# wearable_base.net
KiCad netlist of a schematic drawn in EAGLE
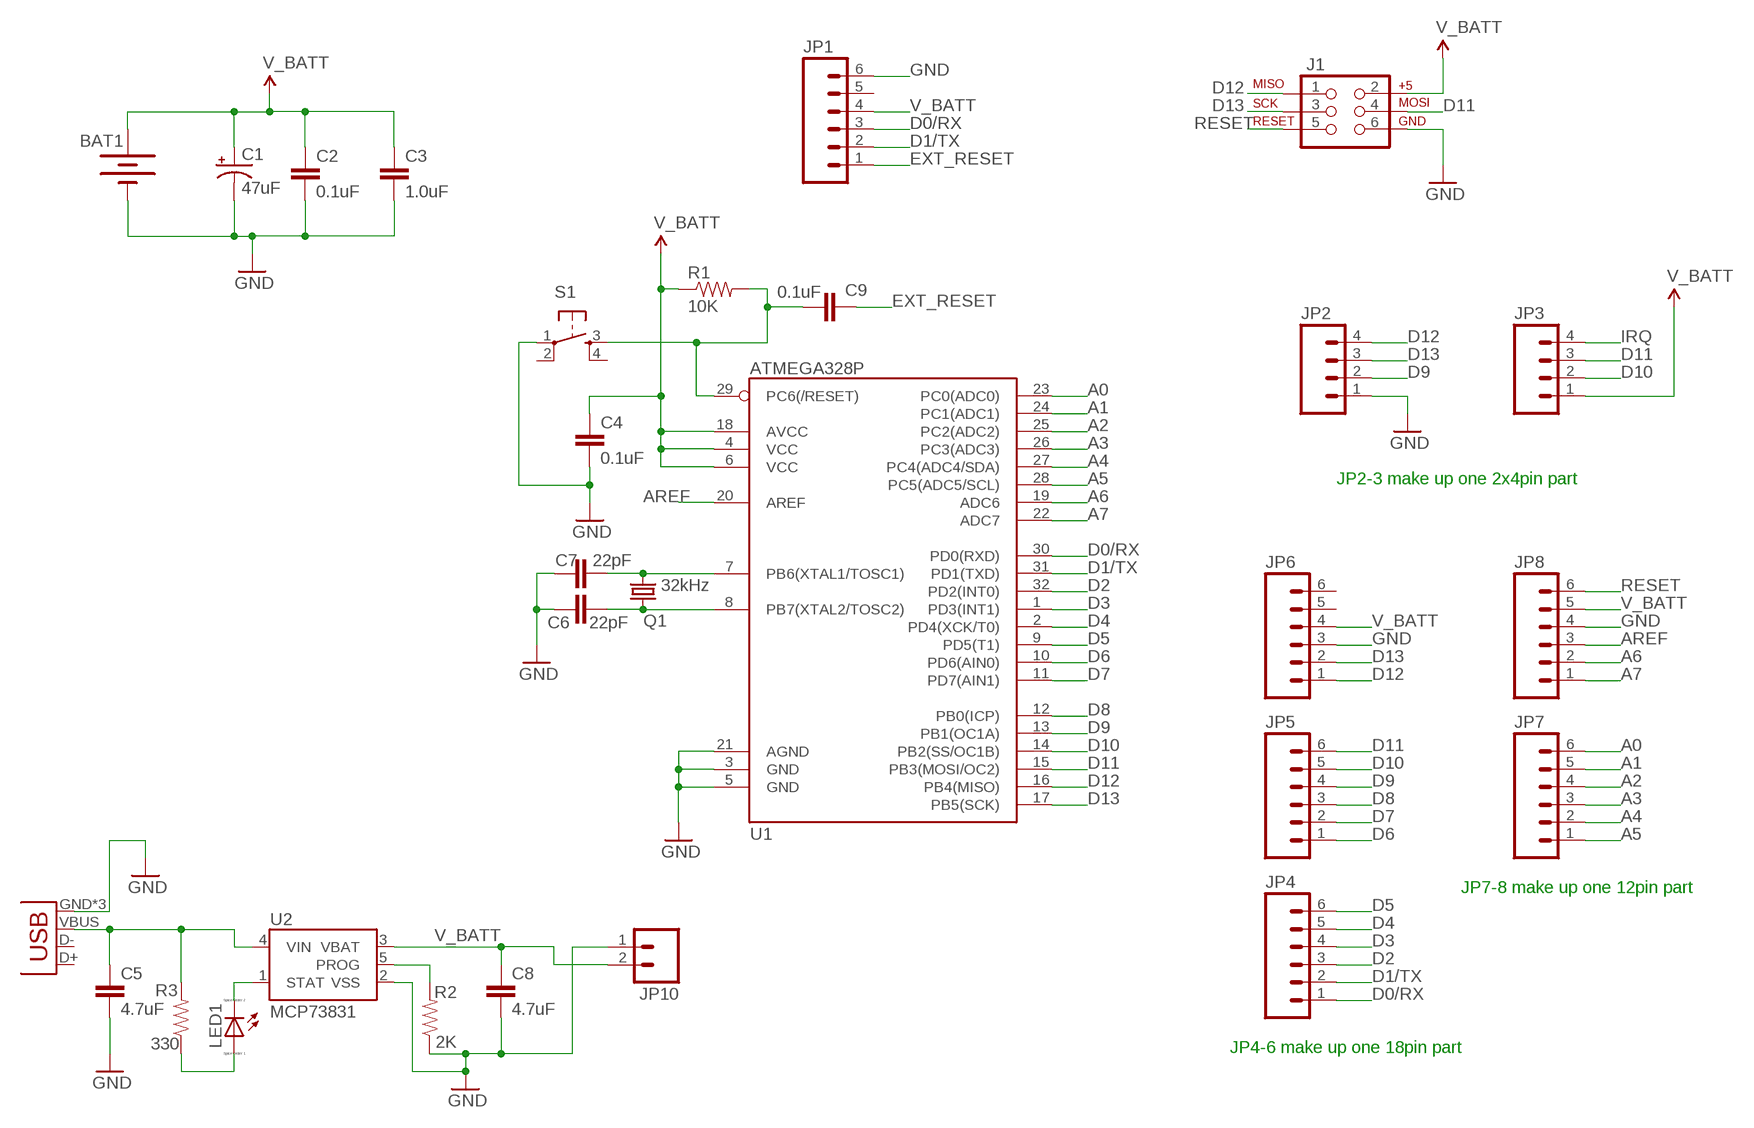
[diagram p0: schematic, sheet 1]

(export (version "E")
  (design (tool "Eeschema 10.0.6"))
  (components
    (comp (ref "BAT1")
      (value "20mm coincell")
      (footprint "eagle-import:BATTCON_20MM_4LEGS")
      (libsource (lib "eagle-import") (part "BATTERY20MM_4LEGS"))
    )
    (comp (ref "C1")
      (value "47uF")
      (footprint "eagle-import:EIA3216")
      (libsource (lib "eagle-import") (part "CAP_POL1206"))
    )
    (comp (ref "C2")
      (value "0.1uF")
      (footprint "eagle-import:0603-CAP")
      (libsource (lib "eagle-import") (part "0.1UF-25V-5%(0603)"))
    )
    (comp (ref "C3")
      (value "1.0uF")
      (footprint "eagle-import:0603-CAP")
      (libsource (lib "eagle-import") (part "1.0UF-16V-10%(0603)"))
    )
    (comp (ref "C4")
      (value "0.1uF")
      (footprint "eagle-import:0603-CAP")
      (libsource (lib "eagle-import") (part "0.1UF-25V-5%(0603)"))
    )
    (comp (ref "C5")
      (value "4.7uF")
      (footprint "eagle-import:0603-CAP")
      (libsource (lib "eagle-import") (part "CAP0603-CAP"))
    )
    (comp (ref "C6")
      (value "22pF")
      (footprint "eagle-import:0603-CAP")
      (libsource (lib "eagle-import") (part "22PF-50V-5%(0603)"))
    )
    (comp (ref "C7")
      (value "22pF")
      (footprint "eagle-import:0603-CAP")
      (libsource (lib "eagle-import") (part "22PF-50V-5%(0603)"))
    )
    (comp (ref "C8")
      (value "4.7uF")
      (footprint "eagle-import:0603-CAP")
      (libsource (lib "eagle-import") (part "CAP0603-CAP"))
    )
    (comp (ref "C9")
      (value "0.1uF")
      (footprint "eagle-import:0603-CAP")
      (libsource (lib "eagle-import") (part "0.1UF-25V-5%(0603)"))
    )
    (comp (ref "J1")
      (value "AVR_SPI_PRG_6PTH")
      (footprint "eagle-import:2X3")
      (libsource (lib "eagle-import") (part "AVR_SPI_PRG_6PTH"))
    )
    (comp (ref "JP1")
      (value "M06SIP")
      (footprint "eagle-import:1X06")
      (libsource (lib "eagle-import") (part "M06SIP"))
    )
    (comp (ref "JP2")
      (value "M04PTH")
      (footprint "eagle-import:1X04")
      (libsource (lib "eagle-import") (part "M04PTH"))
    )
    (comp (ref "JP3")
      (value "M04PTH")
      (footprint "eagle-import:1X04")
      (libsource (lib "eagle-import") (part "M04PTH"))
    )
    (comp (ref "JP4")
      (value "M06SIP")
      (footprint "eagle-import:1X06")
      (libsource (lib "eagle-import") (part "M06SIP"))
    )
    (comp (ref "JP5")
      (value "M06SIP")
      (footprint "eagle-import:1X06")
      (libsource (lib "eagle-import") (part "M06SIP"))
    )
    (comp (ref "JP6")
      (value "M06SIP")
      (footprint "eagle-import:1X06")
      (libsource (lib "eagle-import") (part "M06SIP"))
    )
    (comp (ref "JP7")
      (value "M06SIP")
      (footprint "eagle-import:1X06")
      (libsource (lib "eagle-import") (part "M06SIP"))
    )
    (comp (ref "JP8")
      (value "M06SIP")
      (footprint "eagle-import:1X06")
      (libsource (lib "eagle-import") (part "M06SIP"))
    )
    (comp (ref "JP9")
      (value "USB-MICROB")
      (footprint "eagle-import:USB-MICROB")
      (libsource (lib "eagle-import") (part "USB-MICROB"))
    )
    (comp (ref "JP10")
      (value "M02JST-PTH-2")
      (footprint "eagle-import:JST-2-PTH")
      (libsource (lib "eagle-import") (part "M02JST-PTH-2"))
    )
    (comp (ref "LED1")
      (value "LED_ESML0603")
      (footprint "eagle-import:LED_SML0603")
      (libsource (lib "eagle-import") (part "LED_ESML0603"))
    )
    (comp (ref "Q1")
      (value "32kHz")
      (footprint "eagle-import:TC26H")
      (libsource (lib "eagle-import") (part "CRYSTALTC26H"))
    )
    (comp (ref "R1")
      (value "10K")
      (footprint "eagle-import:0603-RES")
      (libsource (lib "eagle-import") (part "RESISTOR0603-RES"))
    )
    (comp (ref "R2")
      (value "2K")
      (footprint "eagle-import:0603-RES")
      (libsource (lib "eagle-import") (part "RESISTOR0603-RES"))
    )
    (comp (ref "R3")
      (value "330")
      (footprint "eagle-import:0603-RES")
      (libsource (lib "eagle-import") (part "RESISTOR0603-RES"))
    )
    (comp (ref "S1")
      (value "TAC_SWITCHSMD")
      (footprint "eagle-import:TACTILE_SWITCH_SMD")
      (libsource (lib "eagle-import") (part "TAC_SWITCHSMD"))
    )
    (comp (ref "U1")
      (value "ATMEGA328P")
      (footprint "eagle-import:TQFP32-08")
      (libsource (lib "eagle-import") (part "ATMEGA328_SMT"))
    )
    (comp (ref "U2")
      (value "MCP73831")
      (footprint "eagle-import:SOT23-5")
      (libsource (lib "eagle-import") (part "MCP73831"))
    )
  )
  (nets
    (net (code "1") (name "/A0") (class "Default")
      (node (ref "JP7") (pin "6") (pinfunction "6_6") (pintype "passive"))
      (node (ref "U1") (pin "23") (pinfunction "PC0(ADC0)_23") (pintype "bidirectional"))
    )
    (net (code "2") (name "/A1") (class "Default")
      (node (ref "JP7") (pin "5") (pinfunction "5_5") (pintype "passive"))
      (node (ref "U1") (pin "24") (pinfunction "PC1(ADC1)_24") (pintype "bidirectional"))
    )
    (net (code "3") (name "/A2") (class "Default")
      (node (ref "JP7") (pin "4") (pinfunction "4_4") (pintype "passive"))
      (node (ref "U1") (pin "25") (pinfunction "PC2(ADC2)_25") (pintype "bidirectional"))
    )
    (net (code "4") (name "/A3") (class "Default")
      (node (ref "JP7") (pin "3") (pinfunction "3_3") (pintype "passive"))
      (node (ref "U1") (pin "26") (pinfunction "PC3(ADC3)_26") (pintype "bidirectional"))
    )
    (net (code "5") (name "/A4") (class "Default")
      (node (ref "JP7") (pin "2") (pinfunction "2_2") (pintype "passive"))
      (node (ref "U1") (pin "27") (pinfunction "PC4(ADC4/SDA)_27") (pintype "bidirectional"))
    )
    (net (code "6") (name "/A5") (class "Default")
      (node (ref "JP7") (pin "1") (pinfunction "1_1") (pintype "passive"))
      (node (ref "U1") (pin "28") (pinfunction "PC5(ADC5/SCL)_28") (pintype "bidirectional"))
    )
    (net (code "7") (name "/A6") (class "Default")
      (node (ref "JP8") (pin "2") (pinfunction "2_2") (pintype "passive"))
      (node (ref "U1") (pin "19") (pinfunction "ADC6_19") (pintype "bidirectional"))
    )
    (net (code "8") (name "/A7") (class "Default")
      (node (ref "JP8") (pin "1") (pinfunction "1_1") (pintype "passive"))
      (node (ref "U1") (pin "22") (pinfunction "ADC7_22") (pintype "bidirectional"))
    )
    (net (code "9") (name "/AREF") (class "Default")
      (node (ref "JP8") (pin "3") (pinfunction "3_3") (pintype "passive"))
      (node (ref "U1") (pin "20") (pinfunction "AREF_20") (pintype "bidirectional"))
    )
    (net (code "10") (name "/D0{slash}RX") (class "Default")
      (node (ref "JP1") (pin "3") (pinfunction "3_3") (pintype "passive"))
      (node (ref "JP4") (pin "1") (pinfunction "1_1") (pintype "passive"))
      (node (ref "U1") (pin "30") (pinfunction "PD0(RXD)_30") (pintype "bidirectional"))
    )
    (net (code "11") (name "/D1{slash}TX") (class "Default")
      (node (ref "JP1") (pin "2") (pinfunction "2_2") (pintype "passive"))
      (node (ref "JP4") (pin "2") (pinfunction "2_2") (pintype "passive"))
      (node (ref "U1") (pin "31") (pinfunction "PD1(TXD)_31") (pintype "bidirectional"))
    )
    (net (code "12") (name "/D2") (class "Default")
      (node (ref "JP4") (pin "3") (pinfunction "3_3") (pintype "passive"))
      (node (ref "U1") (pin "32") (pinfunction "PD2(INT0)_32") (pintype "bidirectional"))
    )
    (net (code "13") (name "/D3") (class "Default")
      (node (ref "JP4") (pin "4") (pinfunction "4_4") (pintype "passive"))
      (node (ref "U1") (pin "1") (pinfunction "PD3(INT1)_1") (pintype "bidirectional"))
    )
    (net (code "14") (name "/D4") (class "Default")
      (node (ref "JP4") (pin "5") (pinfunction "5_5") (pintype "passive"))
      (node (ref "U1") (pin "2") (pinfunction "PD4(XCK/T0)_2") (pintype "bidirectional"))
    )
    (net (code "15") (name "/D5") (class "Default")
      (node (ref "JP4") (pin "6") (pinfunction "6_6") (pintype "passive"))
      (node (ref "U1") (pin "9") (pinfunction "PD5(T1)_9") (pintype "bidirectional"))
    )
    (net (code "16") (name "/D6") (class "Default")
      (node (ref "JP5") (pin "1") (pinfunction "1_1") (pintype "passive"))
      (node (ref "U1") (pin "10") (pinfunction "PD6(AIN0)_10") (pintype "bidirectional"))
    )
    (net (code "17") (name "/D7") (class "Default")
      (node (ref "JP5") (pin "2") (pinfunction "2_2") (pintype "passive"))
      (node (ref "U1") (pin "11") (pinfunction "PD7(AIN1)_11") (pintype "bidirectional"))
    )
    (net (code "18") (name "/D8") (class "Default")
      (node (ref "JP5") (pin "3") (pinfunction "3_3") (pintype "passive"))
      (node (ref "U1") (pin "12") (pinfunction "PB0(ICP)_12") (pintype "bidirectional"))
    )
    (net (code "19") (name "/D9") (class "Default")
      (node (ref "JP2") (pin "2") (pinfunction "2_2") (pintype "passive"))
      (node (ref "JP5") (pin "4") (pinfunction "4_4") (pintype "passive"))
      (node (ref "U1") (pin "13") (pinfunction "PB1(OC1A)_13") (pintype "bidirectional"))
    )
    (net (code "20") (name "/D10") (class "Default")
      (node (ref "JP3") (pin "2") (pinfunction "2_2") (pintype "passive"))
      (node (ref "JP5") (pin "5") (pinfunction "5_5") (pintype "passive"))
      (node (ref "U1") (pin "14") (pinfunction "PB2(SS/OC1B)_14") (pintype "bidirectional"))
    )
    (net (code "21") (name "/D11") (class "Default")
      (node (ref "J1") (pin "4") (pinfunction "4_4") (pintype "passive"))
      (node (ref "JP3") (pin "3") (pinfunction "3_3") (pintype "passive"))
      (node (ref "JP5") (pin "6") (pinfunction "6_6") (pintype "passive"))
      (node (ref "U1") (pin "15") (pinfunction "PB3(MOSI/OC2)_15") (pintype "bidirectional"))
    )
    (net (code "22") (name "/D12") (class "Default")
      (node (ref "J1") (pin "1") (pinfunction "1_1") (pintype "passive"))
      (node (ref "JP2") (pin "4") (pinfunction "4_4") (pintype "passive"))
      (node (ref "JP6") (pin "1") (pinfunction "1_1") (pintype "passive"))
      (node (ref "U1") (pin "16") (pinfunction "PB4(MISO)_16") (pintype "bidirectional"))
    )
    (net (code "23") (name "/D13") (class "Default")
      (node (ref "J1") (pin "3") (pinfunction "3_3") (pintype "passive"))
      (node (ref "JP2") (pin "3") (pinfunction "3_3") (pintype "passive"))
      (node (ref "JP6") (pin "2") (pinfunction "2_2") (pintype "passive"))
      (node (ref "U1") (pin "17") (pinfunction "PB5(SCK)_17") (pintype "bidirectional"))
    )
    (net (code "24") (name "/EXT_RESET") (class "Default")
      (node (ref "C9") (pin "1") (pinfunction "1_1") (pintype "passive"))
      (node (ref "JP1") (pin "1") (pinfunction "1_1") (pintype "passive"))
    )
    (net (code "25") (name "/IRQ") (class "Default")
      (node (ref "JP3") (pin "4") (pinfunction "4_4") (pintype "passive"))
    )
    (net (code "26") (name "/RESET") (class "Default")
      (node (ref "C9") (pin "2") (pinfunction "2_2") (pintype "passive"))
      (node (ref "J1") (pin "5") (pinfunction "5_5") (pintype "passive"))
      (node (ref "JP8") (pin "6") (pinfunction "6_6") (pintype "passive"))
      (node (ref "R1") (pin "2") (pinfunction "2_2") (pintype "passive"))
      (node (ref "S1") (pin "3") (pinfunction "3_3") (pintype "passive"))
      (node (ref "U1") (pin "29") (pinfunction "PC6(/RESET)_29") (pintype "bidirectional"))
    )
    (net (code "27") (name "GND") (class "Default")
      (node (ref "BAT1") (pin "2") (pinfunction "-_2") (pintype "power_in"))
      (node (ref "C1") (pin "C") (pinfunction "-_C") (pintype "passive"))
      (node (ref "C2") (pin "2") (pinfunction "2_2") (pintype "passive"))
      (node (ref "C3") (pin "2") (pinfunction "2_2") (pintype "passive"))
      (node (ref "C4") (pin "2") (pinfunction "2_2") (pintype "passive"))
      (node (ref "C5") (pin "2") (pinfunction "2_2") (pintype "passive"))
      (node (ref "C6") (pin "1") (pinfunction "1_1") (pintype "passive"))
      (node (ref "C7") (pin "2") (pinfunction "2_2") (pintype "passive"))
      (node (ref "C8") (pin "2") (pinfunction "2_2") (pintype "passive"))
      (node (ref "J1") (pin "6") (pinfunction "6_6") (pintype "passive"))
      (node (ref "JP1") (pin "6") (pinfunction "6_6") (pintype "passive"))
      (node (ref "JP10") (pin "1") (pinfunction "1_1") (pintype "passive"))
      (node (ref "JP2") (pin "1") (pinfunction "1_1") (pintype "passive"))
      (node (ref "JP6") (pin "3") (pinfunction "3_3") (pintype "passive"))
      (node (ref "JP8") (pin "4") (pinfunction "4_4") (pintype "passive"))
      (node (ref "JP9") (pin "GND") (pinfunction "GND_GND") (pintype "bidirectional"))
      (node (ref "JP9") (pin "MT1") (pinfunction "GND_MT1") (pintype "bidirectional"))
      (node (ref "JP9") (pin "MT2") (pinfunction "GND_MT2") (pintype "bidirectional"))
      (node (ref "R2") (pin "1") (pinfunction "1_1") (pintype "passive"))
      (node (ref "S1") (pin "1") (pinfunction "1_1") (pintype "passive"))
      (node (ref "U1") (pin "21") (pinfunction "AGND_21") (pintype "bidirectional"))
      (node (ref "U1") (pin "3") (pinfunction "GND_3") (pintype "bidirectional"))
      (node (ref "U1") (pin "5") (pinfunction "GND_5") (pintype "bidirectional"))
      (node (ref "U2") (pin "2") (pinfunction "VSS_2") (pintype "power_in"))
    )
    (net (code "28") (name "Net-(LED1-PadA)") (class "Default")
      (node (ref "LED1") (pin "A") (pinfunction "A_A") (pintype "passive"))
      (node (ref "R3") (pin "1") (pinfunction "1_1") (pintype "passive"))
    )
    (net (code "29") (name "Net-(U1-PB6(XTAL1{slash}TOSC1))") (class "Default")
      (node (ref "C7") (pin "1") (pinfunction "1_1") (pintype "passive"))
      (node (ref "Q1") (pin "2") (pinfunction "2_2") (pintype "passive"))
      (node (ref "U1") (pin "7") (pinfunction "PB6(XTAL1/TOSC1)_7") (pintype "bidirectional"))
    )
    (net (code "30") (name "Net-(U1-PB7(XTAL2{slash}TOSC2))") (class "Default")
      (node (ref "C6") (pin "2") (pinfunction "2_2") (pintype "passive"))
      (node (ref "Q1") (pin "1") (pinfunction "1_1") (pintype "passive"))
      (node (ref "U1") (pin "8") (pinfunction "PB7(XTAL2/TOSC2)_8") (pintype "bidirectional"))
    )
    (net (code "31") (name "Net-(U2-PROG)") (class "Default")
      (node (ref "R2") (pin "2") (pinfunction "2_2") (pintype "passive"))
      (node (ref "U2") (pin "5") (pinfunction "PROG_5") (pintype "input"))
    )
    (net (code "32") (name "Net-(U2-STAT)") (class "Default")
      (node (ref "LED1") (pin "C") (pinfunction "C_C") (pintype "passive"))
      (node (ref "U2") (pin "1") (pinfunction "STAT_1") (pintype "output"))
    )
    (net (code "33") (name "Net-(U2-VIN)") (class "Default")
      (node (ref "C5") (pin "1") (pinfunction "1_1") (pintype "passive"))
      (node (ref "JP9") (pin "VBUS") (pinfunction "VBUS_VBUS") (pintype "bidirectional"))
      (node (ref "R3") (pin "2") (pinfunction "2_2") (pintype "passive"))
      (node (ref "U2") (pin "4") (pinfunction "VIN_4") (pintype "power_in"))
    )
    (net (code "34") (name "V_BATT") (class "Default")
      (node (ref "BAT1") (pin "1") (pinfunction "+_1") (pintype "power_in"))
      (node (ref "C1") (pin "A") (pinfunction "+_A") (pintype "passive"))
      (node (ref "C2") (pin "1") (pinfunction "1_1") (pintype "passive"))
      (node (ref "C3") (pin "1") (pinfunction "1_1") (pintype "passive"))
      (node (ref "C4") (pin "1") (pinfunction "1_1") (pintype "passive"))
      (node (ref "C8") (pin "1") (pinfunction "1_1") (pintype "passive"))
      (node (ref "J1") (pin "2") (pinfunction "2_2") (pintype "passive"))
      (node (ref "JP1") (pin "4") (pinfunction "4_4") (pintype "passive"))
      (node (ref "JP10") (pin "2") (pinfunction "2_2") (pintype "passive"))
      (node (ref "JP3") (pin "1") (pinfunction "1_1") (pintype "passive"))
      (node (ref "JP6") (pin "4") (pinfunction "4_4") (pintype "passive"))
      (node (ref "JP8") (pin "5") (pinfunction "5_5") (pintype "passive"))
      (node (ref "R1") (pin "1") (pinfunction "1_1") (pintype "passive"))
      (node (ref "U1") (pin "18") (pinfunction "AVCC_18") (pintype "bidirectional"))
      (node (ref "U1") (pin "4") (pinfunction "VCC_4") (pintype "bidirectional"))
      (node (ref "U1") (pin "6") (pinfunction "VCC_6") (pintype "bidirectional"))
      (node (ref "U2") (pin "3") (pinfunction "VBAT_3") (pintype "power_in"))
    )
    (net (code "35") (name "unconnected-(JP1-Pad5)") (class "Default")
      (node (ref "JP1") (pin "5") (pinfunction "5_5") (pintype "passive"))
    )
    (net (code "36") (name "unconnected-(JP6-Pad5)") (class "Default")
      (node (ref "JP6") (pin "5") (pinfunction "5_5") (pintype "passive"))
    )
    (net (code "37") (name "unconnected-(JP6-Pad6)") (class "Default")
      (node (ref "JP6") (pin "6") (pinfunction "6_6") (pintype "passive"))
    )
    (net (code "38") (name "unconnected-(JP9-PadD+)") (class "Default")
      (node (ref "JP9") (pin "D+") (pinfunction "D+_D+") (pintype "bidirectional"))
    )
    (net (code "39") (name "unconnected-(JP9-PadD-)") (class "Default")
      (node (ref "JP9") (pin "D-") (pinfunction "D-_D-") (pintype "bidirectional"))
    )
    (net (code "40") (name "unconnected-(S1-Pad2)") (class "Default")
      (node (ref "S1") (pin "2") (pinfunction "2_2") (pintype "passive"))
    )
    (net (code "41") (name "unconnected-(S1-Pad4)") (class "Default")
      (node (ref "S1") (pin "4") (pinfunction "4_4") (pintype "passive"))
    )
  )
)
